# ElectronPhotonTopBoard.net
KiCad netlist of a schematic drawn in EAGLE
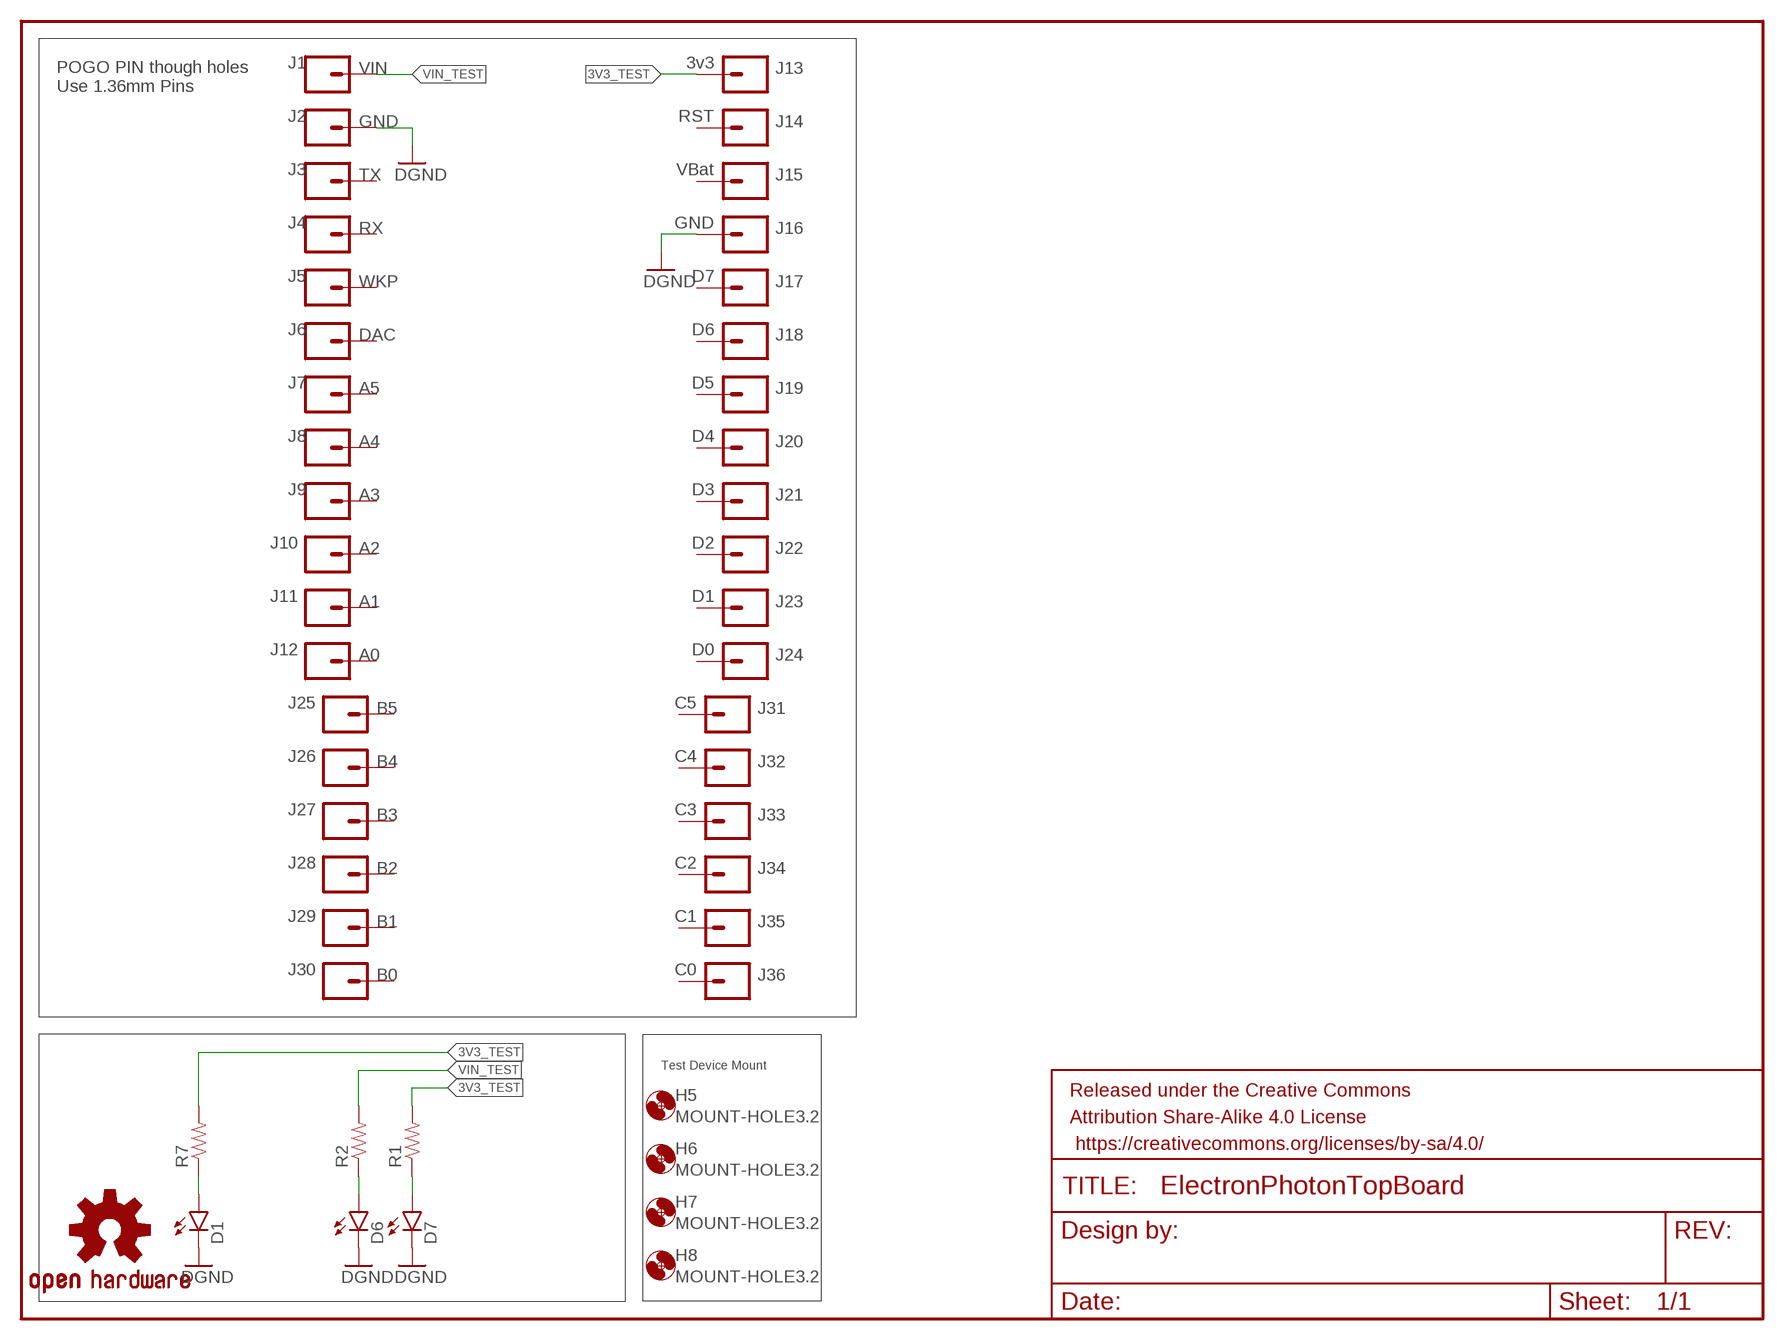
[diagram p0: schematic, sheet 1]

(export (version "E")
  (design (tool "Eeschema 10.0.6"))
  (components
    (comp (ref "D1")
      (value "LED1206-BOTTOM")
      (footprint "eagle-import:LED-1206-BOTTOM")
      (libsource (lib "eagle-import") (part "LED1206-BOTTOM"))
    )
    (comp (ref "D6")
      (value "LED1206-BOTTOM")
      (footprint "eagle-import:LED-1206-BOTTOM")
      (libsource (lib "eagle-import") (part "LED1206-BOTTOM"))
    )
    (comp (ref "D7")
      (value "LED1206-BOTTOM")
      (footprint "eagle-import:LED-1206-BOTTOM")
      (libsource (lib "eagle-import") (part "LED1206-BOTTOM"))
    )
    (comp (ref "FRAME1")
      (value "FRAME-LETTER")
      (footprint "eagle-import:CREATIVE_COMMONS")
      (libsource (lib "eagle-import") (part "FRAME-LETTER"))
    )
    (comp (ref "H5")
      (value "MOUNT-HOLE3.2")
      (footprint "eagle-import:3,2")
      (libsource (lib "eagle-import") (part "MOUNT-HOLE3.2"))
    )
    (comp (ref "H6")
      (value "MOUNT-HOLE3.2")
      (footprint "eagle-import:3,2")
      (libsource (lib "eagle-import") (part "MOUNT-HOLE3.2"))
    )
    (comp (ref "H7")
      (value "MOUNT-HOLE3.2")
      (footprint "eagle-import:3,2")
      (libsource (lib "eagle-import") (part "MOUNT-HOLE3.2"))
    )
    (comp (ref "H8")
      (value "MOUNT-HOLE3.2")
      (footprint "eagle-import:3,2")
      (libsource (lib "eagle-import") (part "MOUNT-HOLE3.2"))
    )
    (comp (ref "J1")
      (value "VIN")
      (footprint "eagle-import:1X01_POGOPIN_HOLE_1.4")
      (libsource (lib "eagle-import") (part "M01-CUSTOMPOGOPIN_HOLE_1.4"))
    )
    (comp (ref "J2")
      (value "GND")
      (footprint "eagle-import:1X01_POGOPIN_HOLE_1.4")
      (libsource (lib "eagle-import") (part "M01-CUSTOMPOGOPIN_HOLE_1.4"))
    )
    (comp (ref "J3")
      (value "TX")
      (footprint "eagle-import:1X01_POGOPIN_HOLE_1.4")
      (libsource (lib "eagle-import") (part "M01-CUSTOMPOGOPIN_HOLE_1.4"))
    )
    (comp (ref "J4")
      (value "RX")
      (footprint "eagle-import:1X01_POGOPIN_HOLE_1.4")
      (libsource (lib "eagle-import") (part "M01-CUSTOMPOGOPIN_HOLE_1.4"))
    )
    (comp (ref "J5")
      (value "WKP")
      (footprint "eagle-import:1X01_POGOPIN_HOLE_1.4")
      (libsource (lib "eagle-import") (part "M01-CUSTOMPOGOPIN_HOLE_1.4"))
    )
    (comp (ref "J6")
      (value "DAC")
      (footprint "eagle-import:1X01_POGOPIN_HOLE_1.4")
      (libsource (lib "eagle-import") (part "M01-CUSTOMPOGOPIN_HOLE_1.4"))
    )
    (comp (ref "J7")
      (value "A5")
      (footprint "eagle-import:1X01_POGOPIN_HOLE_1.4")
      (libsource (lib "eagle-import") (part "M01-CUSTOMPOGOPIN_HOLE_1.4"))
    )
    (comp (ref "J8")
      (value "A4")
      (footprint "eagle-import:1X01_POGOPIN_HOLE_1.4")
      (libsource (lib "eagle-import") (part "M01-CUSTOMPOGOPIN_HOLE_1.4"))
    )
    (comp (ref "J9")
      (value "A3")
      (footprint "eagle-import:1X01_POGOPIN_HOLE_1.4")
      (libsource (lib "eagle-import") (part "M01-CUSTOMPOGOPIN_HOLE_1.4"))
    )
    (comp (ref "J10")
      (value "A2")
      (footprint "eagle-import:1X01_POGOPIN_HOLE_1.4")
      (libsource (lib "eagle-import") (part "M01-CUSTOMPOGOPIN_HOLE_1.4"))
    )
    (comp (ref "J11")
      (value "A1")
      (footprint "eagle-import:1X01_POGOPIN_HOLE_1.4")
      (libsource (lib "eagle-import") (part "M01-CUSTOMPOGOPIN_HOLE_1.4"))
    )
    (comp (ref "J12")
      (value "A0")
      (footprint "eagle-import:1X01_POGOPIN_HOLE_1.4")
      (libsource (lib "eagle-import") (part "M01-CUSTOMPOGOPIN_HOLE_1.4"))
    )
    (comp (ref "J13")
      (value "3v3")
      (footprint "eagle-import:1X01_POGOPIN_HOLE_1.4")
      (libsource (lib "eagle-import") (part "M01-CUSTOMPOGOPIN_HOLE_1.4"))
    )
    (comp (ref "J14")
      (value "RST")
      (footprint "eagle-import:1X01_POGOPIN_HOLE_1.4")
      (libsource (lib "eagle-import") (part "M01-CUSTOMPOGOPIN_HOLE_1.4"))
    )
    (comp (ref "J15")
      (value "VBat")
      (footprint "eagle-import:1X01_POGOPIN_HOLE_1.4")
      (libsource (lib "eagle-import") (part "M01-CUSTOMPOGOPIN_HOLE_1.4"))
    )
    (comp (ref "J16")
      (value "GND")
      (footprint "eagle-import:1X01_POGOPIN_HOLE_1.4")
      (libsource (lib "eagle-import") (part "M01-CUSTOMPOGOPIN_HOLE_1.4"))
    )
    (comp (ref "J17")
      (value "D7")
      (footprint "eagle-import:1X01_POGOPIN_HOLE_1.4")
      (libsource (lib "eagle-import") (part "M01-CUSTOMPOGOPIN_HOLE_1.4"))
    )
    (comp (ref "J18")
      (value "D6")
      (footprint "eagle-import:1X01_POGOPIN_HOLE_1.4")
      (libsource (lib "eagle-import") (part "M01-CUSTOMPOGOPIN_HOLE_1.4"))
    )
    (comp (ref "J19")
      (value "D5")
      (footprint "eagle-import:1X01_POGOPIN_HOLE_1.4")
      (libsource (lib "eagle-import") (part "M01-CUSTOMPOGOPIN_HOLE_1.4"))
    )
    (comp (ref "J20")
      (value "D4")
      (footprint "eagle-import:1X01_POGOPIN_HOLE_1.4")
      (libsource (lib "eagle-import") (part "M01-CUSTOMPOGOPIN_HOLE_1.4"))
    )
    (comp (ref "J21")
      (value "D3")
      (footprint "eagle-import:1X01_POGOPIN_HOLE_1.4")
      (libsource (lib "eagle-import") (part "M01-CUSTOMPOGOPIN_HOLE_1.4"))
    )
    (comp (ref "J22")
      (value "D2")
      (footprint "eagle-import:1X01_POGOPIN_HOLE_1.4")
      (libsource (lib "eagle-import") (part "M01-CUSTOMPOGOPIN_HOLE_1.4"))
    )
    (comp (ref "J23")
      (value "D1")
      (footprint "eagle-import:1X01_POGOPIN_HOLE_1.4")
      (libsource (lib "eagle-import") (part "M01-CUSTOMPOGOPIN_HOLE_1.4"))
    )
    (comp (ref "J24")
      (value "D0")
      (footprint "eagle-import:1X01_POGOPIN_HOLE_1.4")
      (libsource (lib "eagle-import") (part "M01-CUSTOMPOGOPIN_HOLE_1.4"))
    )
    (comp (ref "J25")
      (value "B5")
      (footprint "eagle-import:1X01_POGOPIN_HOLE_1.4")
      (libsource (lib "eagle-import") (part "M01-CUSTOMPOGOPIN_HOLE_1.4"))
    )
    (comp (ref "J26")
      (value "B4")
      (footprint "eagle-import:1X01_POGOPIN_HOLE_1.4")
      (libsource (lib "eagle-import") (part "M01-CUSTOMPOGOPIN_HOLE_1.4"))
    )
    (comp (ref "J27")
      (value "B3")
      (footprint "eagle-import:1X01_POGOPIN_HOLE_1.4")
      (libsource (lib "eagle-import") (part "M01-CUSTOMPOGOPIN_HOLE_1.4"))
    )
    (comp (ref "J28")
      (value "B2")
      (footprint "eagle-import:1X01_POGOPIN_HOLE_1.4")
      (libsource (lib "eagle-import") (part "M01-CUSTOMPOGOPIN_HOLE_1.4"))
    )
    (comp (ref "J29")
      (value "B1")
      (footprint "eagle-import:1X01_POGOPIN_HOLE_1.4")
      (libsource (lib "eagle-import") (part "M01-CUSTOMPOGOPIN_HOLE_1.4"))
    )
    (comp (ref "J30")
      (value "B0")
      (footprint "eagle-import:1X01_POGOPIN_HOLE_1.4")
      (libsource (lib "eagle-import") (part "M01-CUSTOMPOGOPIN_HOLE_1.4"))
    )
    (comp (ref "J31")
      (value "C5")
      (footprint "eagle-import:1X01_POGOPIN_HOLE_1.4")
      (libsource (lib "eagle-import") (part "M01-CUSTOMPOGOPIN_HOLE_1.4"))
    )
    (comp (ref "J32")
      (value "C4")
      (footprint "eagle-import:1X01_POGOPIN_HOLE_1.4")
      (libsource (lib "eagle-import") (part "M01-CUSTOMPOGOPIN_HOLE_1.4"))
    )
    (comp (ref "J33")
      (value "C3")
      (footprint "eagle-import:1X01_POGOPIN_HOLE_1.4")
      (libsource (lib "eagle-import") (part "M01-CUSTOMPOGOPIN_HOLE_1.4"))
    )
    (comp (ref "J34")
      (value "C2")
      (footprint "eagle-import:1X01_POGOPIN_HOLE_1.4")
      (libsource (lib "eagle-import") (part "M01-CUSTOMPOGOPIN_HOLE_1.4"))
    )
    (comp (ref "J35")
      (value "C1")
      (footprint "eagle-import:1X01_POGOPIN_HOLE_1.4")
      (libsource (lib "eagle-import") (part "M01-CUSTOMPOGOPIN_HOLE_1.4"))
    )
    (comp (ref "J36")
      (value "C0")
      (footprint "eagle-import:1X01_POGOPIN_HOLE_1.4")
      (libsource (lib "eagle-import") (part "M01-CUSTOMPOGOPIN_HOLE_1.4"))
    )
    (comp (ref "LOGO1")
      (value "OSHW-LOGOL")
      (footprint "eagle-import:OSHW-LOGO-L")
      (libsource (lib "eagle-import") (part "OSHW-LOGOL"))
    )
    (comp (ref "R1")
      (value "RESISTOR1206")
      (footprint "eagle-import:1206")
      (libsource (lib "eagle-import") (part "RESISTOR1206"))
    )
    (comp (ref "R2")
      (value "RESISTOR1206")
      (footprint "eagle-import:1206")
      (libsource (lib "eagle-import") (part "RESISTOR1206"))
    )
    (comp (ref "R7")
      (value "RESISTOR1206")
      (footprint "eagle-import:1206")
      (libsource (lib "eagle-import") (part "RESISTOR1206"))
    )
  )
  (nets
    (net (code "1") (name "3V3_TEST") (class "Default")
      (node (ref "J13") (pin "1") (pinfunction "1_1") (pintype "passive"))
      (node (ref "R1") (pin "2") (pinfunction "2_2") (pintype "passive"))
      (node (ref "R7") (pin "2") (pinfunction "2_2") (pintype "passive"))
    )
    (net (code "2") (name "DGND") (class "Default")
      (node (ref "D1") (pin "C") (pinfunction "C_C") (pintype "passive"))
      (node (ref "D6") (pin "C") (pinfunction "C_C") (pintype "passive"))
      (node (ref "D7") (pin "C") (pinfunction "C_C") (pintype "passive"))
      (node (ref "J16") (pin "1") (pinfunction "1_1") (pintype "passive"))
      (node (ref "J2") (pin "1") (pinfunction "1_1") (pintype "passive"))
    )
    (net (code "3") (name "Net-(D1-PadA)") (class "Default")
      (node (ref "D1") (pin "A") (pinfunction "A_A") (pintype "passive"))
      (node (ref "R7") (pin "1") (pinfunction "1_1") (pintype "passive"))
    )
    (net (code "4") (name "Net-(D6-PadA)") (class "Default")
      (node (ref "D6") (pin "A") (pinfunction "A_A") (pintype "passive"))
      (node (ref "R2") (pin "1") (pinfunction "1_1") (pintype "passive"))
    )
    (net (code "5") (name "Net-(D7-PadA)") (class "Default")
      (node (ref "D7") (pin "A") (pinfunction "A_A") (pintype "passive"))
      (node (ref "R1") (pin "1") (pinfunction "1_1") (pintype "passive"))
    )
    (net (code "6") (name "VIN_TEST") (class "Default")
      (node (ref "J1") (pin "1") (pinfunction "1_1") (pintype "passive"))
      (node (ref "R2") (pin "2") (pinfunction "2_2") (pintype "passive"))
    )
    (net (code "7") (name "unconnected-(J3-Pad1)") (class "Default")
      (node (ref "J3") (pin "1") (pinfunction "1_1") (pintype "passive"))
    )
    (net (code "8") (name "unconnected-(J4-Pad1)") (class "Default")
      (node (ref "J4") (pin "1") (pinfunction "1_1") (pintype "passive"))
    )
    (net (code "9") (name "unconnected-(J5-Pad1)") (class "Default")
      (node (ref "J5") (pin "1") (pinfunction "1_1") (pintype "passive"))
    )
    (net (code "10") (name "unconnected-(J6-Pad1)") (class "Default")
      (node (ref "J6") (pin "1") (pinfunction "1_1") (pintype "passive"))
    )
    (net (code "11") (name "unconnected-(J7-Pad1)") (class "Default")
      (node (ref "J7") (pin "1") (pinfunction "1_1") (pintype "passive"))
    )
    (net (code "12") (name "unconnected-(J8-Pad1)") (class "Default")
      (node (ref "J8") (pin "1") (pinfunction "1_1") (pintype "passive"))
    )
    (net (code "13") (name "unconnected-(J9-Pad1)") (class "Default")
      (node (ref "J9") (pin "1") (pinfunction "1_1") (pintype "passive"))
    )
    (net (code "14") (name "unconnected-(J10-Pad1)") (class "Default")
      (node (ref "J10") (pin "1") (pinfunction "1_1") (pintype "passive"))
    )
    (net (code "15") (name "unconnected-(J11-Pad1)") (class "Default")
      (node (ref "J11") (pin "1") (pinfunction "1_1") (pintype "passive"))
    )
    (net (code "16") (name "unconnected-(J12-Pad1)") (class "Default")
      (node (ref "J12") (pin "1") (pinfunction "1_1") (pintype "passive"))
    )
    (net (code "17") (name "unconnected-(J14-Pad1)") (class "Default")
      (node (ref "J14") (pin "1") (pinfunction "1_1") (pintype "passive"))
    )
    (net (code "18") (name "unconnected-(J15-Pad1)") (class "Default")
      (node (ref "J15") (pin "1") (pinfunction "1_1") (pintype "passive"))
    )
    (net (code "19") (name "unconnected-(J17-Pad1)") (class "Default")
      (node (ref "J17") (pin "1") (pinfunction "1_1") (pintype "passive"))
    )
    (net (code "20") (name "unconnected-(J18-Pad1)") (class "Default")
      (node (ref "J18") (pin "1") (pinfunction "1_1") (pintype "passive"))
    )
    (net (code "21") (name "unconnected-(J19-Pad1)") (class "Default")
      (node (ref "J19") (pin "1") (pinfunction "1_1") (pintype "passive"))
    )
    (net (code "22") (name "unconnected-(J20-Pad1)") (class "Default")
      (node (ref "J20") (pin "1") (pinfunction "1_1") (pintype "passive"))
    )
    (net (code "23") (name "unconnected-(J21-Pad1)") (class "Default")
      (node (ref "J21") (pin "1") (pinfunction "1_1") (pintype "passive"))
    )
    (net (code "24") (name "unconnected-(J22-Pad1)") (class "Default")
      (node (ref "J22") (pin "1") (pinfunction "1_1") (pintype "passive"))
    )
    (net (code "25") (name "unconnected-(J23-Pad1)") (class "Default")
      (node (ref "J23") (pin "1") (pinfunction "1_1") (pintype "passive"))
    )
    (net (code "26") (name "unconnected-(J24-Pad1)") (class "Default")
      (node (ref "J24") (pin "1") (pinfunction "1_1") (pintype "passive"))
    )
    (net (code "27") (name "unconnected-(J25-Pad1)") (class "Default")
      (node (ref "J25") (pin "1") (pinfunction "1_1") (pintype "passive"))
    )
    (net (code "28") (name "unconnected-(J26-Pad1)") (class "Default")
      (node (ref "J26") (pin "1") (pinfunction "1_1") (pintype "passive"))
    )
    (net (code "29") (name "unconnected-(J27-Pad1)") (class "Default")
      (node (ref "J27") (pin "1") (pinfunction "1_1") (pintype "passive"))
    )
    (net (code "30") (name "unconnected-(J28-Pad1)") (class "Default")
      (node (ref "J28") (pin "1") (pinfunction "1_1") (pintype "passive"))
    )
    (net (code "31") (name "unconnected-(J29-Pad1)") (class "Default")
      (node (ref "J29") (pin "1") (pinfunction "1_1") (pintype "passive"))
    )
    (net (code "32") (name "unconnected-(J30-Pad1)") (class "Default")
      (node (ref "J30") (pin "1") (pinfunction "1_1") (pintype "passive"))
    )
    (net (code "33") (name "unconnected-(J31-Pad1)") (class "Default")
      (node (ref "J31") (pin "1") (pinfunction "1_1") (pintype "passive"))
    )
    (net (code "34") (name "unconnected-(J32-Pad1)") (class "Default")
      (node (ref "J32") (pin "1") (pinfunction "1_1") (pintype "passive"))
    )
    (net (code "35") (name "unconnected-(J33-Pad1)") (class "Default")
      (node (ref "J33") (pin "1") (pinfunction "1_1") (pintype "passive"))
    )
    (net (code "36") (name "unconnected-(J34-Pad1)") (class "Default")
      (node (ref "J34") (pin "1") (pinfunction "1_1") (pintype "passive"))
    )
    (net (code "37") (name "unconnected-(J35-Pad1)") (class "Default")
      (node (ref "J35") (pin "1") (pinfunction "1_1") (pintype "passive"))
    )
    (net (code "38") (name "unconnected-(J36-Pad1)") (class "Default")
      (node (ref "J36") (pin "1") (pinfunction "1_1") (pintype "passive"))
    )
  )
)
